# MEMS_RF.net
KiCad netlist of a schematic drawn in Altium Designer
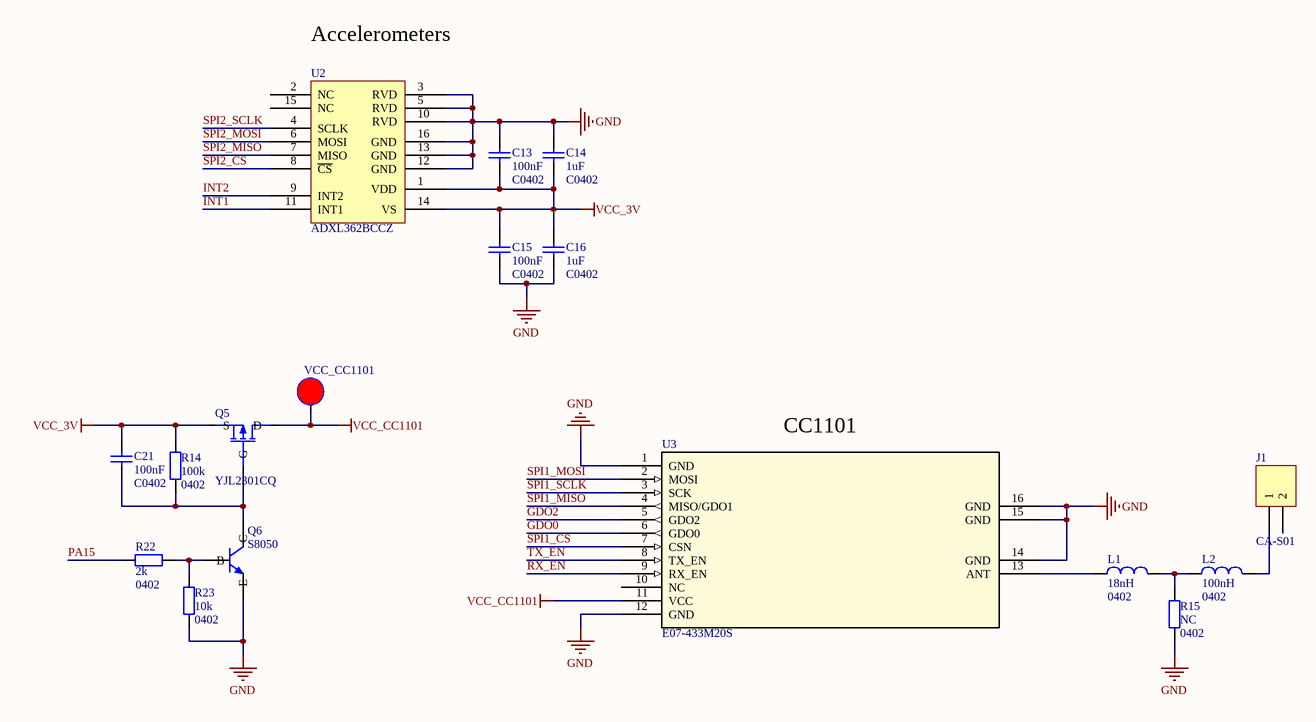
[diagram p0: MEMS&RF.SchDoc]

(export (version "E")
  (design (tool "Eeschema 10.0.6"))
  (components
    (comp (ref "C13")
      (value "100nF")
      (footprint "0402")
      (description "Capacitor (0402,X7R,100nF,DC 50V,±10%) Murata")
      (fields (field (name "PACKAGEREFERENCE") "C0402") (field (name "PUBLISHER") "Altium Limited"))
      (libsource (lib "RFID_CC1101_433MHz") (part "GRM155R71H104KE14"))
    )
    (comp (ref "C14")
      (value "1uF")
      (footprint "0402")
      (description "Capacitor (0402,X5R,1uF,DC 25V,±10%) Murata")
      (fields (field (name "PACKAGEREFERENCE") "C0402") (field (name "PUBLISHER") "Altium Limited"))
      (libsource (lib "RFID_CC1101_433MHz") (part "GRM155R61E105KE11"))
    )
    (comp (ref "C15")
      (value "100nF")
      (footprint "0402")
      (description "Capacitor (0402,X7R,100nF,DC 50V,±10%) Murata")
      (fields (field (name "PACKAGEREFERENCE") "C0402") (field (name "PUBLISHER") "Altium Limited"))
      (libsource (lib "RFID_CC1101_433MHz") (part "GRM155R71H104KE14"))
    )
    (comp (ref "C16")
      (value "1uF")
      (footprint "0402")
      (description "Capacitor (0402,X5R,1uF,DC 25V,±10%) Murata")
      (fields (field (name "PACKAGEREFERENCE") "C0402") (field (name "PUBLISHER") "Altium Limited"))
      (libsource (lib "RFID_CC1101_433MHz") (part "GRM155R61E105KE11"))
    )
    (comp (ref "C21")
      (value "100nF")
      (footprint "0402")
      (description "Capacitor (0402,X7R,100nF,DC 50V,±10%) Murata")
      (fields (field (name "PACKAGEREFERENCE") "C0402") (field (name "PUBLISHER") "Altium Limited"))
      (libsource (lib "RFID_CC1101_433MHz") (part "GRM155R71H104KE14"))
    )
    (comp (ref "J1")
      (value "CA-S01")
      (footprint "CA-S01")
      (description "CrossAir Antenna，广州寒武纪电子科技有限公司")
      (fields (field (name "PUBLISHER") "Altium Limited"))
      (libsource (lib "RFID_CC1101_433MHz") (part "CA-S01"))
    )
    (comp (ref "L1")
      (value "18nH")
      (footprint "0402")
      (description "Inductor, 18n, 0402, ±5%, wire-wound type Murata")
      (fields (field (name "PACKAGEREFERENCE") "0402") (field (name "PUBLISHER") "Altium Limited"))
      (libsource (lib "PhoenixPCBLIB") (part "LQW15AN18NJ00"))
    )
    (comp (ref "L2")
      (value "100nH")
      (footprint "0402")
      (description "Inductor, 100n, 0402, ±5%, wire-wound type Murata")
      (fields (field (name "PACKAGEREFERENCE") "0402") (field (name "PUBLISHER") "Altium Limited"))
      (libsource (lib "RFID_CC1101_433MHz") (part "LQW15ANR10J00"))
    )
    (comp (ref "Q5")
      (value "YJL2301CQ")
      (footprint "SOT95P237X112-3N")
      (fields (field (name "PUBLISHER") "Altium Limited"))
      (libsource (lib "PhoenixPCBLIB") (part "YJL2301CQ"))
    )
    (comp (ref "Q6")
      (value "S8050")
      (footprint "SOT-23B_N")
      (description "NPN General Purpose Amplifier, -55 to +150°C")
      (fields (field (name "MANUFACTURER") "扬州扬杰电子科技股份有限公司"))
      (libsource (lib "RFID_CC1101_433MHz") (part "S8050"))
    )
    (comp (ref "R14")
      (value "100k")
      (footprint "RESC1005X04N")
      (description "Resistor 0402(1005) 100kΩ ±1%")
      (fields (field (name "PACKAGEREFERENCE") "0402"))
      (libsource (lib "BC26_GNSS") (part "RC0402FR-07100KL"))
    )
    (comp (ref "R15")
      (value "NC")
      (footprint "RESC1005X04N")
      (description "Resistor 0402(1005) 0Ω")
      (fields (field (name "PACKAGEREFERENCE") "0402"))
      (libsource (lib "RFID_CC1101_433MHz") (part "RC0402JR"))
    )
    (comp (ref "R22")
      (value "2k")
      (footprint "RESC1005X04N")
      (description "Resistor 0402(1005) 2kΩ ±1%")
      (fields (field (name "PACKAGEREFERENCE") "0402"))
      (libsource (lib "BC26_GNSS") (part "RC0402FR-072KL"))
    )
    (comp (ref "R23")
      (value "10k")
      (footprint "RESC1005X04N")
      (description "Resistor 0402(1005) 10kΩ ±1%")
      (fields (field (name "PACKAGEREFERENCE") "0402"))
      (libsource (lib "BC26_GNSS") (part "RC0402FR-0710KL"))
    )
    (comp (ref "U2")
      (value "ADXL362BCCZ")
      (footprint "LGA_CC-16-4")
      (description "ADXL362, LGA, CC-16-4.")
      (libsource (lib "GPS_NB") (part "ADXL362BCCZ"))
    )
    (comp (ref "U3")
      (value "E07-433M20S")
      (footprint "PE07-433M20S")
      (libsource (lib "RFID_CC1101_433MHz") (part "E07-433M20S"))
    )
    (comp (ref "VCC_CC1101")
      (value "TP-EMB-SMT-Single-20mil-1pin")
      (footprint "EMB-SMT-40MILX40MIL")
      (description "Test Point Designed for holding a standard probe lead")
      (libsource (lib "BC26_GNSS") (part "TP-EMB-SMT-Single-20mil-1pin"))
    )
  )
  (nets
    (net (code "1") (name "/GDO0") (class "Default")
      (node (ref "U3") (pin "6") (pinfunction "GDO0_6") (pintype "output"))
    )
    (net (code "2") (name "/GDO2") (class "Default")
      (node (ref "U3") (pin "5") (pinfunction "GDO2_5") (pintype "output"))
    )
    (net (code "3") (name "/INT1") (class "Default")
      (node (ref "U2") (pin "11") (pinfunction "INT1_11") (pintype "passive"))
    )
    (net (code "4") (name "/INT2") (class "Default")
      (node (ref "U2") (pin "9") (pinfunction "INT2_9") (pintype "passive"))
    )
    (net (code "5") (name "/PA15") (class "Default")
      (node (ref "R22") (pin "1") (pinfunction "1_1") (pintype "passive"))
    )
    (net (code "6") (name "/RX_EN") (class "Default")
      (node (ref "U3") (pin "9") (pinfunction "RX_EN_9") (pintype "input"))
    )
    (net (code "7") (name "/SPI1_CS") (class "Default")
      (node (ref "U3") (pin "7") (pinfunction "CSN_7") (pintype "input"))
    )
    (net (code "8") (name "/SPI1_MISO") (class "Default")
      (node (ref "U3") (pin "4") (pinfunction "MISO/GDO1_4") (pintype "output"))
    )
    (net (code "9") (name "/SPI1_MOSI") (class "Default")
      (node (ref "U3") (pin "2") (pinfunction "MOSI_2") (pintype "input"))
    )
    (net (code "10") (name "/SPI1_SCLK") (class "Default")
      (node (ref "U3") (pin "3") (pinfunction "SCK_3") (pintype "input"))
    )
    (net (code "11") (name "/SPI2_CS") (class "Default")
      (node (ref "U2") (pin "8") (pinfunction "~{CS}_8") (pintype "passive"))
    )
    (net (code "12") (name "/SPI2_MISO") (class "Default")
      (node (ref "U2") (pin "7") (pinfunction "MISO_7") (pintype "passive"))
    )
    (net (code "13") (name "/SPI2_MOSI") (class "Default")
      (node (ref "U2") (pin "6") (pinfunction "MOSI_6") (pintype "passive"))
    )
    (net (code "14") (name "/SPI2_SCLK") (class "Default")
      (node (ref "U2") (pin "4") (pinfunction "SCLK_4") (pintype "passive"))
    )
    (net (code "15") (name "/TX_EN") (class "Default")
      (node (ref "U3") (pin "8") (pinfunction "TX_EN_8") (pintype "input"))
    )
    (net (code "16") (name "GND") (class "Default")
      (node (ref "C13") (pin "2") (pinfunction "2_2") (pintype "passive"))
      (node (ref "C14") (pin "2") (pinfunction "2_2") (pintype "passive"))
      (node (ref "C15") (pin "2") (pinfunction "2_2") (pintype "passive"))
      (node (ref "C16") (pin "1") (pinfunction "1_1") (pintype "passive"))
      (node (ref "Q6") (pin "E") (pinfunction "E_E") (pintype "passive"))
      (node (ref "R15") (pin "1") (pinfunction "1_1") (pintype "passive"))
      (node (ref "R23") (pin "1") (pinfunction "1_1") (pintype "passive"))
      (node (ref "U2") (pin "10") (pinfunction "RVD_10") (pintype "passive"))
      (node (ref "U2") (pin "12") (pinfunction "GND_12") (pintype "passive"))
      (node (ref "U2") (pin "13") (pinfunction "GND_13") (pintype "passive"))
      (node (ref "U2") (pin "16") (pinfunction "GND_16") (pintype "passive"))
      (node (ref "U2") (pin "3") (pinfunction "RVD_3") (pintype "passive"))
      (node (ref "U2") (pin "5") (pinfunction "RVD_5") (pintype "passive"))
      (node (ref "U3") (pin "1") (pinfunction "GND_1") (pintype "power_in"))
      (node (ref "U3") (pin "12") (pinfunction "GND_12") (pintype "power_in"))
      (node (ref "U3") (pin "14") (pinfunction "GND_14") (pintype "power_in"))
      (node (ref "U3") (pin "15") (pinfunction "GND_15") (pintype "power_in"))
      (node (ref "U3") (pin "16") (pinfunction "GND_16") (pintype "power_in"))
    )
    (net (code "17") (name "Net-(J1-Pad1)") (class "Default")
      (node (ref "J1") (pin "1") (pinfunction "1_1") (pintype "passive"))
      (node (ref "L2") (pin "2") (pinfunction "2_2") (pintype "passive"))
    )
    (net (code "18") (name "Net-(L1-Pad2)") (class "Default")
      (node (ref "L1") (pin "2") (pinfunction "2_2") (pintype "passive"))
      (node (ref "L2") (pin "1") (pinfunction "1_1") (pintype "passive"))
      (node (ref "R15") (pin "2") (pinfunction "2_2") (pintype "passive"))
    )
    (net (code "19") (name "Net-(Q5-G)") (class "Default")
      (node (ref "C21") (pin "2") (pinfunction "2_2") (pintype "passive"))
      (node (ref "Q5") (pin "1") (pinfunction "G_1") (pintype "passive"))
      (node (ref "Q6") (pin "C") (pinfunction "C_C") (pintype "passive"))
      (node (ref "R14") (pin "1") (pinfunction "1_1") (pintype "passive"))
    )
    (net (code "20") (name "Net-(Q6-PadB)") (class "Default")
      (node (ref "Q6") (pin "B") (pinfunction "B_B") (pintype "passive"))
      (node (ref "R22") (pin "2") (pinfunction "2_2") (pintype "passive"))
      (node (ref "R23") (pin "2") (pinfunction "2_2") (pintype "passive"))
    )
    (net (code "21") (name "Net-(U3-ANT)") (class "Default")
      (node (ref "L1") (pin "1") (pinfunction "1_1") (pintype "passive"))
      (node (ref "U3") (pin "13") (pinfunction "ANT_13") (pintype "passive"))
    )
    (net (code "22") (name "VCC_3V") (class "Default")
      (node (ref "C13") (pin "1") (pinfunction "1_1") (pintype "passive"))
      (node (ref "C14") (pin "1") (pinfunction "1_1") (pintype "passive"))
      (node (ref "C15") (pin "1") (pinfunction "1_1") (pintype "passive"))
      (node (ref "C16") (pin "2") (pinfunction "2_2") (pintype "passive"))
      (node (ref "C21") (pin "1") (pinfunction "1_1") (pintype "passive"))
      (node (ref "Q5") (pin "2") (pinfunction "S_2") (pintype "passive"))
      (node (ref "R14") (pin "2") (pinfunction "2_2") (pintype "passive"))
      (node (ref "U2") (pin "1") (pinfunction "VDD_1") (pintype "passive"))
      (node (ref "U2") (pin "14") (pinfunction "VS_14") (pintype "passive"))
    )
    (net (code "23") (name "VCC_CC1101") (class "Default")
      (node (ref "Q5") (pin "3") (pinfunction "D_3") (pintype "passive"))
      (node (ref "U3") (pin "11") (pinfunction "VCC_11") (pintype "power_in"))
      (node (ref "VCC_CC1101") (pin "1") (pinfunction "1_1") (pintype "passive"))
    )
    (net (code "24") (name "unconnected-(J1-Pad2)") (class "Default")
      (node (ref "J1") (pin "2") (pinfunction "2_2") (pintype "passive"))
    )
    (net (code "25") (name "unconnected-(U2-NC-Pad2)") (class "Default")
      (node (ref "U2") (pin "2") (pinfunction "NC_2") (pintype "passive"))
    )
    (net (code "26") (name "unconnected-(U2-NC-Pad15)") (class "Default")
      (node (ref "U2") (pin "15") (pinfunction "NC_15") (pintype "passive"))
    )
    (net (code "27") (name "unconnected-(U3-NC-Pad10)") (class "Default")
      (node (ref "U3") (pin "10") (pinfunction "NC_10") (pintype "passive"))
    )
  )
)
